# GMSL_DESERIALIZER.net
KiCad netlist of a schematic drawn in Altium Designer
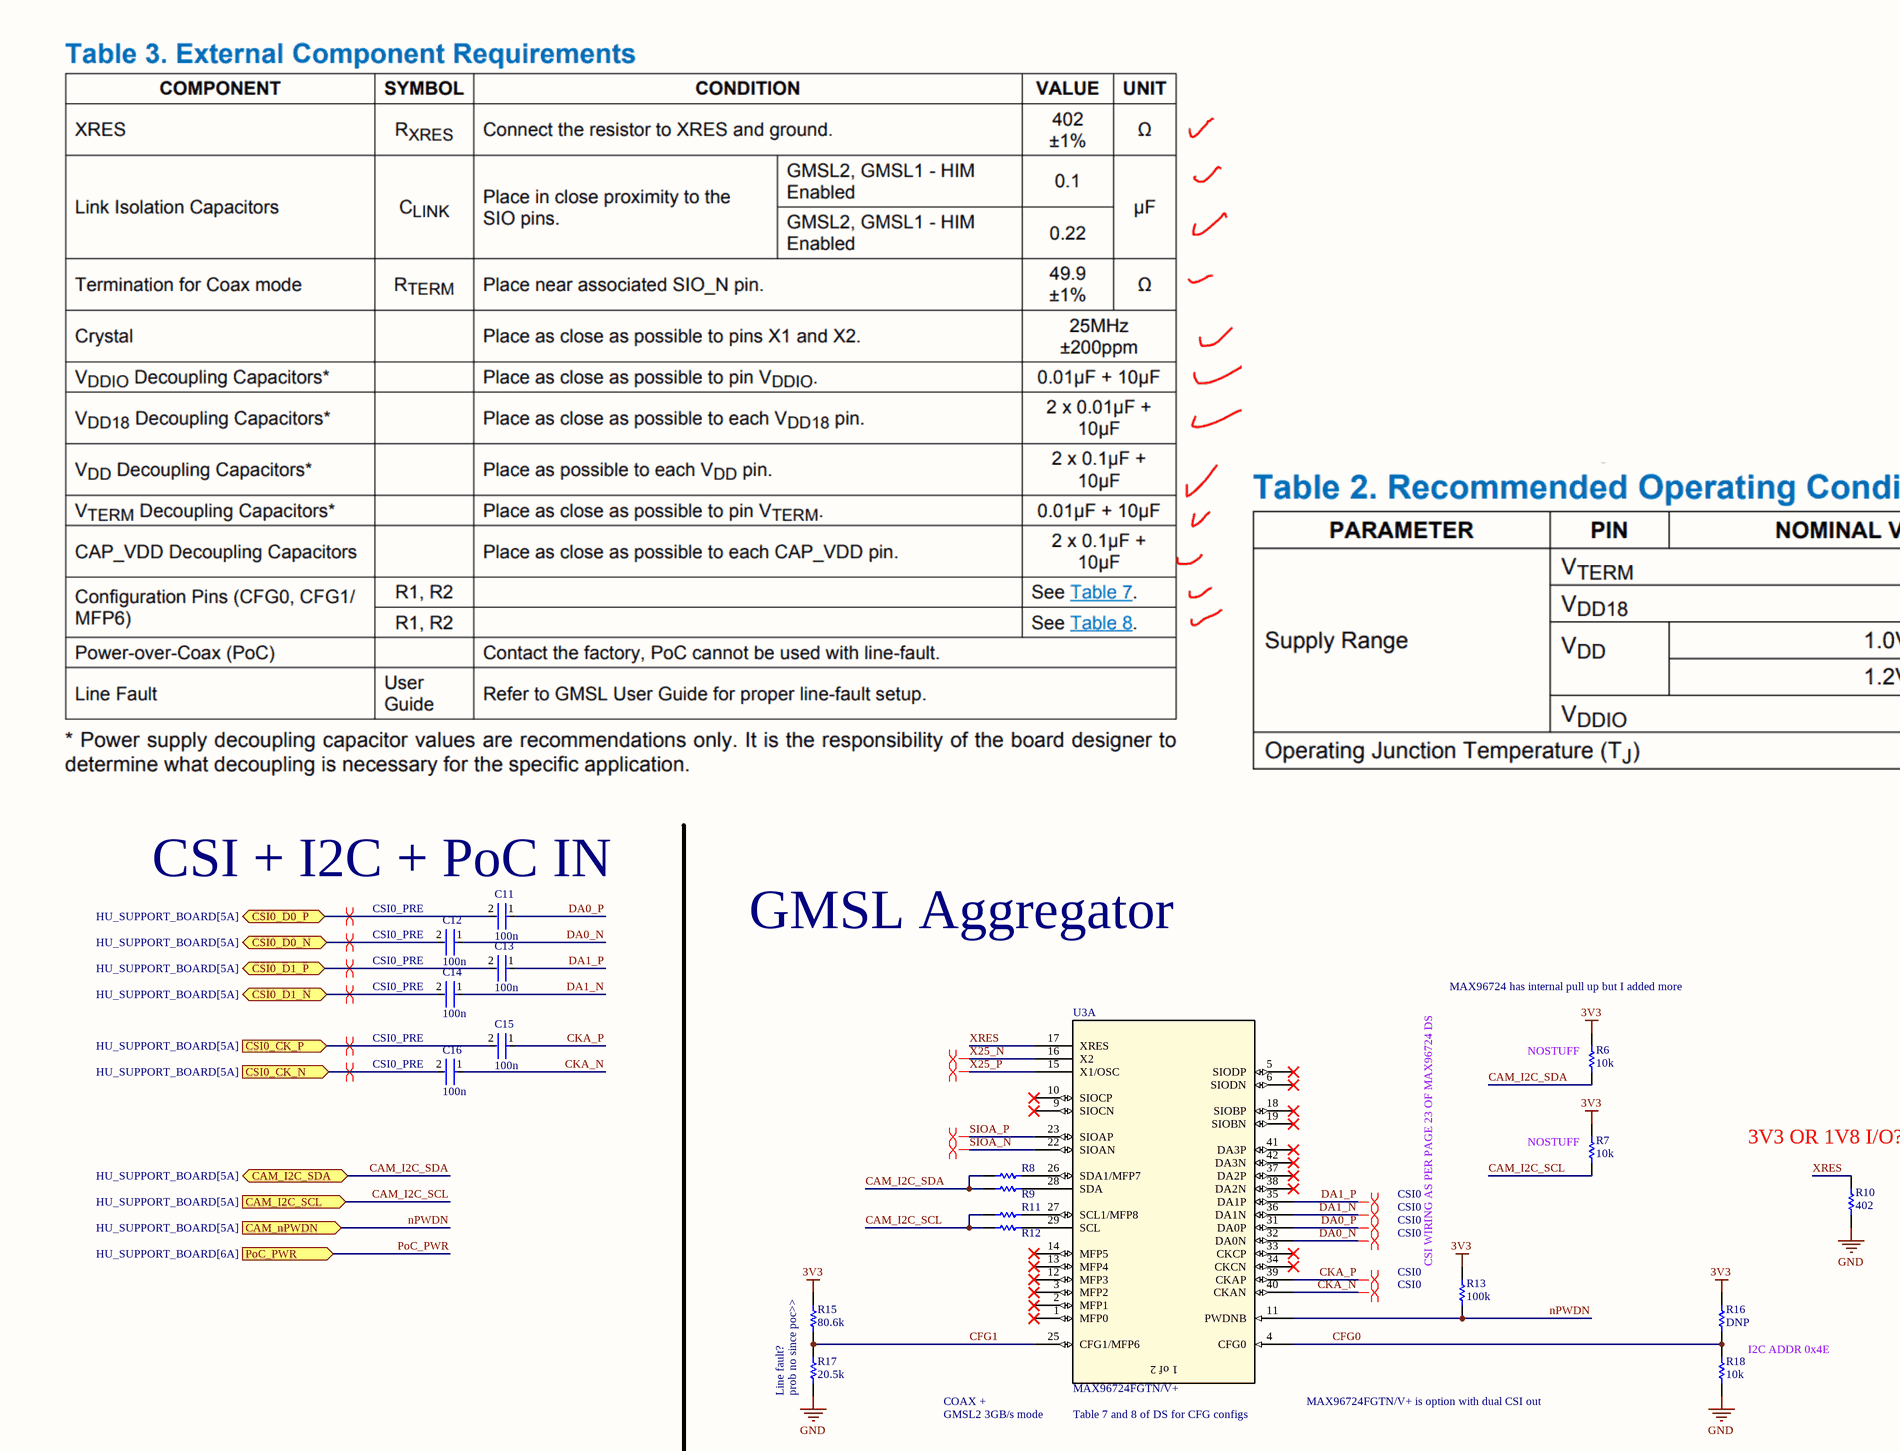
[diagram p0: GMSL_DESERIALIZER.SchDoc, top left]
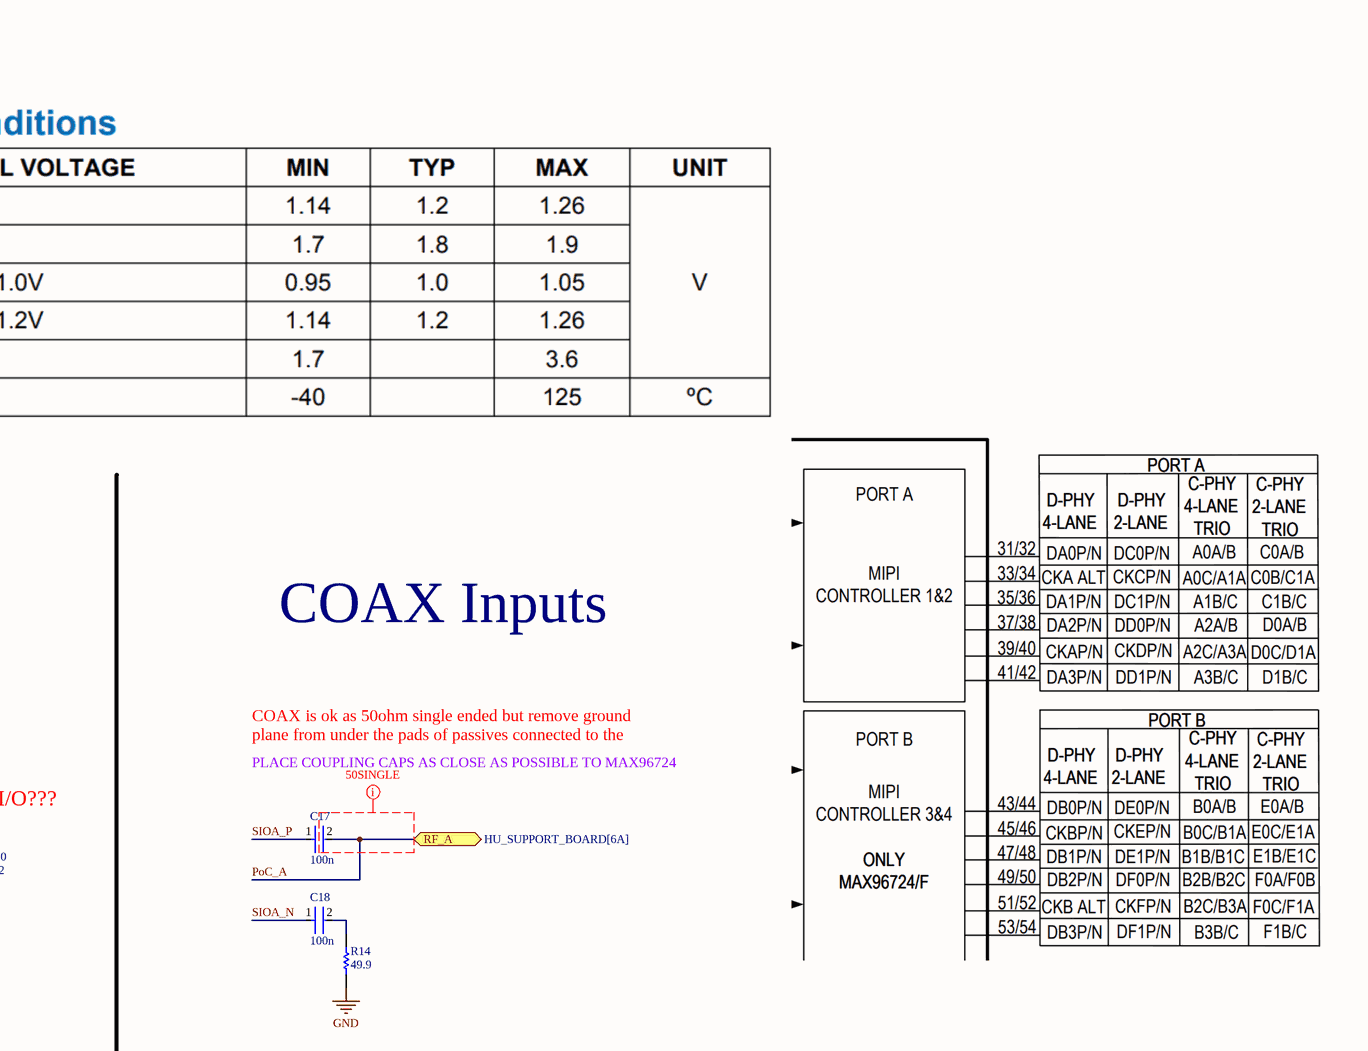
[diagram p1: GMSL_DESERIALIZER.SchDoc, top right]
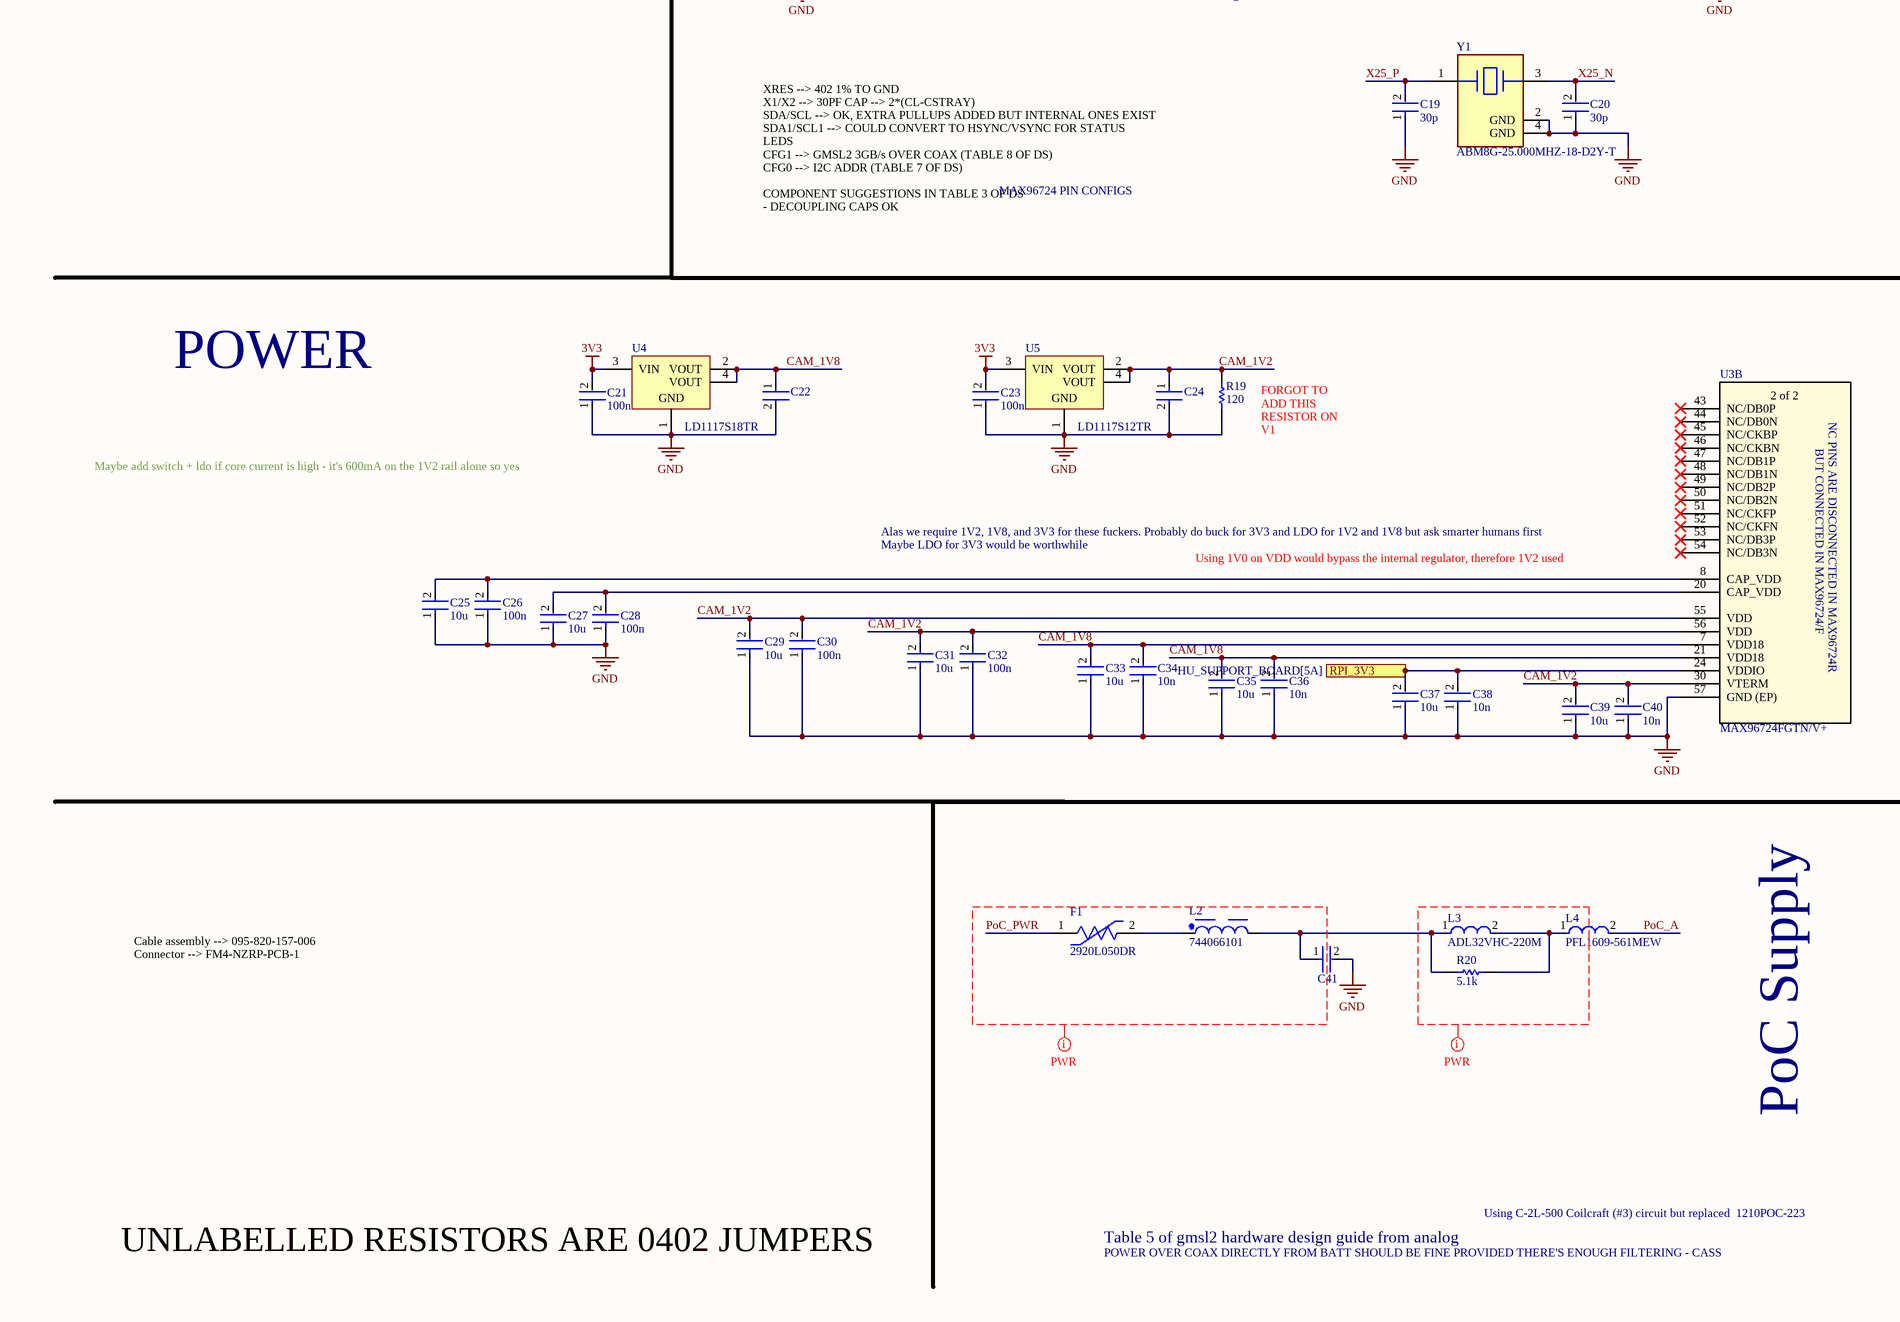
[diagram p2: GMSL_DESERIALIZER.SchDoc, bottom left]
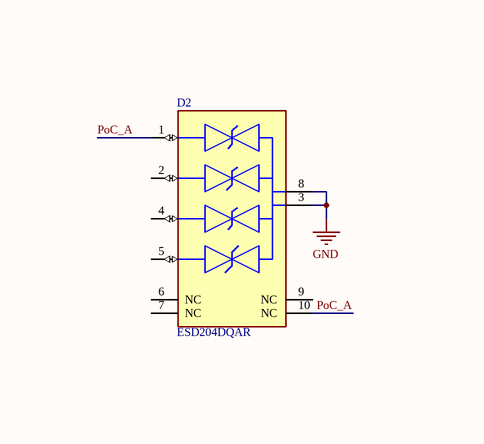
[diagram p3: GMSL_DESERIALIZER.SchDoc, bottom right]

(export (version "E")
  (design (tool "Eeschema 10.0.6"))
  (components
    (comp (ref "C11")
      (value "100n")
      (footprint "FP-0402-L_1_0_0_05-W_0_5-IPC_A")
      (description "LARGE PADS, 0402 CAP, CHANGE COMMENT TO MATCH REAL P/N")
      (libsource (lib "Space Concordia") (part "b4654b650e69147ec39a6b967a45e02"))
    )
    (comp (ref "C12")
      (value "100n")
      (footprint "FP-0402-L_1_0_0_05-W_0_5-IPC_A")
      (description "LARGE PADS, 0402 CAP, CHANGE COMMENT TO MATCH REAL P/N")
      (libsource (lib "Space Concordia") (part "b4654b650e69147ec39a6b967a45e02"))
    )
    (comp (ref "C13")
      (value "100n")
      (footprint "FP-0402-L_1_0_0_05-W_0_5-IPC_A")
      (description "LARGE PADS, 0402 CAP, CHANGE COMMENT TO MATCH REAL P/N")
      (libsource (lib "Space Concordia") (part "b4654b650e69147ec39a6b967a45e02"))
    )
    (comp (ref "C14")
      (value "100n")
      (footprint "FP-0402-L_1_0_0_05-W_0_5-IPC_A")
      (description "LARGE PADS, 0402 CAP, CHANGE COMMENT TO MATCH REAL P/N")
      (libsource (lib "Space Concordia") (part "b4654b650e69147ec39a6b967a45e02"))
    )
    (comp (ref "C15")
      (value "100n")
      (footprint "FP-0402-L_1_0_0_05-W_0_5-IPC_A")
      (description "LARGE PADS, 0402 CAP, CHANGE COMMENT TO MATCH REAL P/N")
      (libsource (lib "Space Concordia") (part "b4654b650e69147ec39a6b967a45e02"))
    )
    (comp (ref "C16")
      (value "100n")
      (footprint "FP-0402-L_1_0_0_05-W_0_5-IPC_A")
      (description "LARGE PADS, 0402 CAP, CHANGE COMMENT TO MATCH REAL P/N")
      (libsource (lib "Space Concordia") (part "b4654b650e69147ec39a6b967a45e02"))
    )
    (comp (ref "C17")
      (value "100n")
      (footprint "FP-0402-L_1_0_0_05-W_0_5-IPC_A")
      (description "LARGE PADS, 0402 CAP, CHANGE COMMENT TO MATCH REAL P/N")
      (libsource (lib "Space Concordia") (part "b4654b650e69147ec39a6b967a45e02"))
    )
    (comp (ref "C18")
      (value "100n")
      (footprint "FP-0402-L_1_0_0_05-W_0_5-IPC_A")
      (description "LARGE PADS, 0402 CAP, CHANGE COMMENT TO MATCH REAL P/N")
      (libsource (lib "Space Concordia") (part "b4654b650e69147ec39a6b967a45e02"))
    )
    (comp (ref "C19")
      (value "30p")
      (footprint "FP-0402-L_1_0_0_05-W_0_5-IPC_A")
      (description "LARGE PADS, 0402 CAP, CHANGE COMMENT TO MATCH REAL P/N")
      (libsource (lib "Space Concordia") (part "b4654b650e69147ec39a6b967a45e02"))
    )
    (comp (ref "C20")
      (value "30p")
      (footprint "FP-0402-L_1_0_0_05-W_0_5-IPC_A")
      (description "LARGE PADS, 0402 CAP, CHANGE COMMENT TO MATCH REAL P/N")
      (libsource (lib "Space Concordia") (part "b4654b650e69147ec39a6b967a45e02"))
    )
    (comp (ref "C21")
      (value "100n")
      (footprint "FP-0402-L_1_0_0_05-W_0_5-IPC_A")
      (description "LARGE PADS, 0402 CAP, CHANGE COMMENT TO MATCH REAL P/N")
      (libsource (lib "Space Concordia") (part "b4654b650e69147ec39a6b967a45e02"))
    )
    (comp (ref "C22")
      (value "GRM188R60J106ME47D")
      (footprint "FP-GRM188-0_1-e0_2_0_55-IPC_A")
      (description "Chip Multilayer Ceramic Capacitors for General Purpose, 0603, 10uF, X5R, 15%, 20%, 6.3V")
      (fields (field (name "VOLTAGE") "6.3V") (field (name "TOLERANCE") "20%"))
      (libsource (lib "Altium Content Vault") (part "02cd4be3c70576c341d710602a673aa"))
    )
    (comp (ref "C23")
      (value "100n")
      (footprint "FP-0402-L_1_0_0_05-W_0_5-IPC_A")
      (description "LARGE PADS, 0402 CAP, CHANGE COMMENT TO MATCH REAL P/N")
      (libsource (lib "Space Concordia") (part "b4654b650e69147ec39a6b967a45e02"))
    )
    (comp (ref "C24")
      (value "GRM188R60J106ME47D")
      (footprint "FP-GRM188-0_1-e0_2_0_55-IPC_A")
      (description "Chip Multilayer Ceramic Capacitors for General Purpose, 0603, 10uF, X5R, 15%, 20%, 6.3V")
      (fields (field (name "VOLTAGE") "6.3V") (field (name "TOLERANCE") "20%"))
      (libsource (lib "Altium Content Vault") (part "02cd4be3c70576c341d710602a673aa"))
    )
    (comp (ref "C25")
      (value "10u")
      (footprint "FP-0402-L_1_0_0_05-W_0_5-IPC_A")
      (description "LARGE PADS, 0402 CAP, CHANGE COMMENT TO MATCH REAL P/N")
      (libsource (lib "Space Concordia") (part "b4654b650e69147ec39a6b967a45e02"))
    )
    (comp (ref "C26")
      (value "100n")
      (footprint "FP-0402-L_1_0_0_05-W_0_5-IPC_A")
      (description "LARGE PADS, 0402 CAP, CHANGE COMMENT TO MATCH REAL P/N")
      (libsource (lib "Space Concordia") (part "b4654b650e69147ec39a6b967a45e02"))
    )
    (comp (ref "C27")
      (value "10u")
      (footprint "FP-0402-L_1_0_0_05-W_0_5-IPC_A")
      (description "LARGE PADS, 0402 CAP, CHANGE COMMENT TO MATCH REAL P/N")
      (libsource (lib "Space Concordia") (part "b4654b650e69147ec39a6b967a45e02"))
    )
    (comp (ref "C28")
      (value "100n")
      (footprint "FP-0402-L_1_0_0_05-W_0_5-IPC_A")
      (description "LARGE PADS, 0402 CAP, CHANGE COMMENT TO MATCH REAL P/N")
      (libsource (lib "Space Concordia") (part "b4654b650e69147ec39a6b967a45e02"))
    )
    (comp (ref "C29")
      (value "10u")
      (footprint "FP-0402-L_1_0_0_05-W_0_5-IPC_A")
      (description "LARGE PADS, 0402 CAP, CHANGE COMMENT TO MATCH REAL P/N")
      (libsource (lib "Space Concordia") (part "b4654b650e69147ec39a6b967a45e02"))
    )
    (comp (ref "C30")
      (value "100n")
      (footprint "FP-0402-L_1_0_0_05-W_0_5-IPC_A")
      (description "LARGE PADS, 0402 CAP, CHANGE COMMENT TO MATCH REAL P/N")
      (libsource (lib "Space Concordia") (part "b4654b650e69147ec39a6b967a45e02"))
    )
    (comp (ref "C31")
      (value "10u")
      (footprint "FP-0402-L_1_0_0_05-W_0_5-IPC_A")
      (description "LARGE PADS, 0402 CAP, CHANGE COMMENT TO MATCH REAL P/N")
      (libsource (lib "Space Concordia") (part "b4654b650e69147ec39a6b967a45e02"))
    )
    (comp (ref "C32")
      (value "100n")
      (footprint "FP-0402-L_1_0_0_05-W_0_5-IPC_A")
      (description "LARGE PADS, 0402 CAP, CHANGE COMMENT TO MATCH REAL P/N")
      (libsource (lib "Space Concordia") (part "b4654b650e69147ec39a6b967a45e02"))
    )
    (comp (ref "C33")
      (value "10u")
      (footprint "FP-0402-L_1_0_0_05-W_0_5-IPC_A")
      (description "LARGE PADS, 0402 CAP, CHANGE COMMENT TO MATCH REAL P/N")
      (libsource (lib "Space Concordia") (part "b4654b650e69147ec39a6b967a45e02"))
    )
    (comp (ref "C34")
      (value "10n")
      (footprint "FP-0402-L_1_0_0_05-W_0_5-IPC_A")
      (description "LARGE PADS, 0402 CAP, CHANGE COMMENT TO MATCH REAL P/N")
      (libsource (lib "Space Concordia") (part "b4654b650e69147ec39a6b967a45e02"))
    )
    (comp (ref "C35")
      (value "10u")
      (footprint "FP-0402-L_1_0_0_05-W_0_5-IPC_A")
      (description "LARGE PADS, 0402 CAP, CHANGE COMMENT TO MATCH REAL P/N")
      (libsource (lib "Space Concordia") (part "b4654b650e69147ec39a6b967a45e02"))
    )
    (comp (ref "C36")
      (value "10n")
      (footprint "FP-0402-L_1_0_0_05-W_0_5-IPC_A")
      (description "LARGE PADS, 0402 CAP, CHANGE COMMENT TO MATCH REAL P/N")
      (libsource (lib "Space Concordia") (part "b4654b650e69147ec39a6b967a45e02"))
    )
    (comp (ref "C37")
      (value "10u")
      (footprint "FP-0402-L_1_0_0_05-W_0_5-IPC_A")
      (description "LARGE PADS, 0402 CAP, CHANGE COMMENT TO MATCH REAL P/N")
      (libsource (lib "Space Concordia") (part "b4654b650e69147ec39a6b967a45e02"))
    )
    (comp (ref "C38")
      (value "10n")
      (footprint "FP-0402-L_1_0_0_05-W_0_5-IPC_A")
      (description "LARGE PADS, 0402 CAP, CHANGE COMMENT TO MATCH REAL P/N")
      (libsource (lib "Space Concordia") (part "b4654b650e69147ec39a6b967a45e02"))
    )
    (comp (ref "C39")
      (value "10u")
      (footprint "FP-0402-L_1_0_0_05-W_0_5-IPC_A")
      (description "LARGE PADS, 0402 CAP, CHANGE COMMENT TO MATCH REAL P/N")
      (libsource (lib "Space Concordia") (part "b4654b650e69147ec39a6b967a45e02"))
    )
    (comp (ref "C40")
      (value "10n")
      (footprint "FP-0402-L_1_0_0_05-W_0_5-IPC_A")
      (description "LARGE PADS, 0402 CAP, CHANGE COMMENT TO MATCH REAL P/N")
      (libsource (lib "Space Concordia") (part "b4654b650e69147ec39a6b967a45e02"))
    )
    (comp (ref "C41")
      (value "GRM21BR61E226ME44L")
      (footprint "FP-GRM21B-0_2-e0_2_0_7-IPC_B")
      (description "Chip Multilayer Ceramic Capacitors for General Purpose, 0805, 22uF, X5R, 15%, 20%, 25V")
      (fields (field (name "TOLERANCE") "20%") (field (name "VOLTAGE") "25V"))
      (libsource (lib "Altium Content Vault") (part "b4654b650e69147ec39a6b967a45e02"))
    )
    (comp (ref "D2")
      (value "ESD204DQAR")
      (footprint "FP-DQA0010A-MFG")
      (description "4-CHANNEL LOW-CAPACITANCE SURGE")
      (fields
        (field (name "MANUFACTURER") "Texas Instruments")
        (field (name "OCTOPART") "https://octopart.com/esd204dqar-texas+instruments-89917476")
      )
      (libsource (lib "Altium Content Vault") (part "1465e58c1818c7767b55926832f0bf5"))
    )
    (comp (ref "F1")
      (value "2920L050DR")
      (footprint "FP-2920L050DR-MFG")
      (description "PTC RESET FUSE 60V 500MA 2920")
      (libsource (lib "Altium Content Vault") (part "1c6d77a0208143737455a0c7eb396be"))
    )
    (comp (ref "L2")
      (value "744066101")
      (footprint "WE-TPC_1038")
      (fields (field (name "TOLERANCE") "30%"))
      (libsource (lib "Altium Content Vault") (part "Inductor - 2"))
    )
    (comp (ref "L3")
      (value "ADL32VHC-220M")
      (footprint "FP-1210POC-MFG")
      (description "NOT COILCRAFT - ACTUAL P# --> ADL32VHC-220M\r\n - Power Injection Chokes for PoC")
      (fields
        (field (name "MANUFACTURER") "coilcraft")
        (field (name "OCTOPART") "https://octopart.com/1210poc-223mrc-coilcraft-103207315")
      )
      (libsource (lib "Altium Content Vault") (part "725321dda6339637d4d059423bc1c3c"))
    )
    (comp (ref "L4")
      (value "PFL1609-561MEW")
      (footprint "FP-PFL1609-MFG")
      (description "Fixed Inductors PFL1609 Low Profile 0.56 uH 20 % 1.4 A")
      (fields (field (name "MANUFACTURER") "coilcraft") (field (name "TOLERANCE") "20%"))
      (libsource (lib "Altium Content Vault") (part "725321dda6339637d4d059423bc1c3c"))
    )
    (comp (ref "R6")
      (value "10k")
      (footprint "R0603B")
      (description "Resistor")
      (libsource (lib "Space Concordia") (part "Resistor"))
    )
    (comp (ref "R7")
      (value "10k")
      (footprint "R0603B")
      (description "Resistor")
      (libsource (lib "Space Concordia") (part "Resistor"))
    )
    (comp (ref "R8")
      (value "0402 JUMPER")
      (footprint "RESC1005X40X25ML05T05")
      (description "READ THE NAME")
      (libsource (lib "Space Concordia") (part "CMP-009-00206-2"))
    )
    (comp (ref "R9")
      (value "0402 JUMPER")
      (footprint "RESC1005X40X25ML05T05")
      (description "READ THE NAME")
      (libsource (lib "Space Concordia") (part "CMP-009-00206-2"))
    )
    (comp (ref "R10")
      (value "402")
      (footprint "R0603B")
      (description "Resistor")
      (libsource (lib "Space Concordia") (part "Resistor"))
    )
    (comp (ref "R11")
      (value "0402 JUMPER")
      (footprint "RESC1005X40X25ML05T05")
      (description "READ THE NAME")
      (libsource (lib "Space Concordia") (part "CMP-009-00206-2"))
    )
    (comp (ref "R12")
      (value "0402 JUMPER")
      (footprint "RESC1005X40X25ML05T05")
      (description "READ THE NAME")
      (libsource (lib "Space Concordia") (part "CMP-009-00206-2"))
    )
    (comp (ref "R13")
      (value "100k")
      (footprint "R0603B")
      (description "Resistor")
      (libsource (lib "Space Concordia") (part "Resistor"))
    )
    (comp (ref "R14")
      (value "49.9")
      (footprint "R0603B")
      (description "Resistor")
      (libsource (lib "Space Concordia") (part "Resistor"))
    )
    (comp (ref "R15")
      (value "80.6k")
      (footprint "R0603B")
      (description "Resistor")
      (libsource (lib "Space Concordia") (part "Resistor"))
    )
    (comp (ref "R16")
      (value "DNP")
      (footprint "R0603B")
      (description "Resistor")
      (libsource (lib "Space Concordia") (part "Resistor"))
    )
    (comp (ref "R17")
      (value "20.5k")
      (footprint "R0603B")
      (description "Resistor")
      (libsource (lib "Space Concordia") (part "Resistor"))
    )
    (comp (ref "R18")
      (value "10k")
      (footprint "R0603B")
      (description "Resistor")
      (libsource (lib "Space Concordia") (part "Resistor"))
    )
    (comp (ref "R19")
      (value "120")
      (footprint "R0603B")
      (description "Resistor")
      (libsource (lib "Space Concordia") (part "Resistor"))
    )
    (comp (ref "R20")
      (value "5.1k")
      (footprint "R0603B")
      (description "Resistor")
      (libsource (lib "Space Concordia") (part "Resistor"))
    )
    (comp (ref "U3")
      (value "MAX96724FGTN/V+")
      (footprint "MAX96724FGTN_V+-Footprint-1")
      (description "Quad Tunneling GMSL2/1 to CSI-2 Deserializer")
      (libsource (lib "") (part "MAX96724FGTN_V+-Symbol-1_1"))
    )
    (comp (ref "U4")
      (value "LD1117S18TR")
      (footprint "SOT-223_M")
      (description "Fixed Low Drop Positive Voltage Regulator, 1.8V, 4-Pin SOT-223, Tape and Reel")
      (libsource (lib "Altium Content Vault") (part "PM-REG-LD1117-SOT4"))
    )
    (comp (ref "U5")
      (value "LD1117S12TR")
      (footprint "SOT-223_M")
      (description "Fixed Low Drop Positive Voltage Regulator, 1.2V, 4-Pin SOT-223, Tape and Reel")
      (libsource (lib "Altium Content Vault") (part "PM-REG-LD1117-SOT4"))
    )
    (comp (ref "Y1")
      (value "ABM8G-25.000MHZ-18-D2Y-T")
      (footprint "FP-ABM8G-MFG")
      (description "Crystal 25MHz ±20ppm (Tol) ±30ppm (Stability) 18pF FUND 60Ω 4-Pin SMD T/R")
      (fields (field (name "TOLERANCE") "20ppm"))
      (libsource (lib "Altium Content Vault") (part "48e526d86b7f2615d98721063c72f49"))
    )
  )
  (nets
    (net (code "1") (name "/CAM_1V2") (class "Default")
      (node (ref "C24") (pin "1") (pinfunction "1_1") (pintype "passive"))
      (node (ref "C29") (pin "2") (pinfunction "2_2") (pintype "passive"))
      (node (ref "C30") (pin "2") (pinfunction "2_2") (pintype "passive"))
      (node (ref "C31") (pin "2") (pinfunction "2_2") (pintype "passive"))
      (node (ref "C32") (pin "2") (pinfunction "2_2") (pintype "passive"))
      (node (ref "C39") (pin "2") (pinfunction "2_2") (pintype "passive"))
      (node (ref "C40") (pin "2") (pinfunction "2_2") (pintype "passive"))
      (node (ref "R19") (pin "1") (pinfunction "1_1") (pintype "passive"))
      (node (ref "U3") (pin "30") (pinfunction "VTERM_30") (pintype "power_in"))
      (node (ref "U3") (pin "55") (pinfunction "VDD_55") (pintype "power_in"))
      (node (ref "U3") (pin "56") (pinfunction "VDD_56") (pintype "power_in"))
      (node (ref "U5") (pin "2") (pinfunction "VOUT_2") (pintype "power_in"))
      (node (ref "U5") (pin "4") (pinfunction "VOUT_4") (pintype "power_in"))
    )
    (net (code "2") (name "/CAM_1V8") (class "Default")
      (node (ref "C22") (pin "1") (pinfunction "1_1") (pintype "passive"))
      (node (ref "C33") (pin "2") (pinfunction "2_2") (pintype "passive"))
      (node (ref "C34") (pin "2") (pinfunction "2_2") (pintype "passive"))
      (node (ref "C35") (pin "2") (pinfunction "2_2") (pintype "passive"))
      (node (ref "C36") (pin "2") (pinfunction "2_2") (pintype "passive"))
      (node (ref "U3") (pin "21") (pinfunction "VDD18_21") (pintype "power_in"))
      (node (ref "U3") (pin "7") (pinfunction "VDD18_7") (pintype "power_in"))
      (node (ref "U4") (pin "2") (pinfunction "VOUT_2") (pintype "power_in"))
      (node (ref "U4") (pin "4") (pinfunction "VOUT_4") (pintype "power_in"))
    )
    (net (code "3") (name "/CAM_I2C_SCL") (class "Default")
      (node (ref "R11") (pin "1") (pinfunction "1_1") (pintype "passive"))
      (node (ref "R12") (pin "1") (pinfunction "1_1") (pintype "passive"))
      (node (ref "R7") (pin "1") (pinfunction "1_1") (pintype "passive"))
    )
    (net (code "4") (name "/CAM_I2C_SDA") (class "Default")
      (node (ref "R6") (pin "1") (pinfunction "1_1") (pintype "passive"))
      (node (ref "R8") (pin "1") (pinfunction "1_1") (pintype "passive"))
      (node (ref "R9") (pin "1") (pinfunction "1_1") (pintype "passive"))
    )
    (net (code "5") (name "/CFG0") (class "Default")
      (node (ref "R16") (pin "1") (pinfunction "1_1") (pintype "passive"))
      (node (ref "R18") (pin "2") (pinfunction "2_2") (pintype "passive"))
      (node (ref "U3") (pin "4") (pinfunction "CFG0_4") (pintype "input"))
    )
    (net (code "6") (name "/CFG1") (class "Default")
      (node (ref "R15") (pin "1") (pinfunction "1_1") (pintype "passive"))
      (node (ref "R17") (pin "2") (pinfunction "2_2") (pintype "passive"))
      (node (ref "U3") (pin "25") (pinfunction "CFG1/MFP6_25") (pintype "bidirectional"))
    )
    (net (code "7") (name "/CKA_N") (class "Default")
      (node (ref "C16") (pin "1") (pinfunction "1_1") (pintype "passive"))
      (node (ref "U3") (pin "40") (pinfunction "CKAN_40") (pintype "bidirectional"))
    )
    (net (code "8") (name "/CKA_P") (class "Default")
      (node (ref "C15") (pin "1") (pinfunction "1_1") (pintype "passive"))
      (node (ref "U3") (pin "39") (pinfunction "CKAP_39") (pintype "bidirectional"))
    )
    (net (code "9") (name "/CSI0_CK_N") (class "Default")
      (node (ref "C16") (pin "2") (pinfunction "2_2") (pintype "passive"))
    )
    (net (code "10") (name "/CSI0_CK_P") (class "Default")
      (node (ref "C15") (pin "2") (pinfunction "2_2") (pintype "passive"))
    )
    (net (code "11") (name "/CSI0_D0_N") (class "Default")
      (node (ref "C12") (pin "2") (pinfunction "2_2") (pintype "passive"))
    )
    (net (code "12") (name "/CSI0_D0_P") (class "Default")
      (node (ref "C11") (pin "2") (pinfunction "2_2") (pintype "passive"))
    )
    (net (code "13") (name "/CSI0_D1_N") (class "Default")
      (node (ref "C14") (pin "2") (pinfunction "2_2") (pintype "passive"))
    )
    (net (code "14") (name "/CSI0_D1_P") (class "Default")
      (node (ref "C13") (pin "2") (pinfunction "2_2") (pintype "passive"))
    )
    (net (code "15") (name "/DA0_N") (class "Default")
      (node (ref "C12") (pin "1") (pinfunction "1_1") (pintype "passive"))
      (node (ref "U3") (pin "32") (pinfunction "DA0N_32") (pintype "bidirectional"))
    )
    (net (code "16") (name "/DA0_P") (class "Default")
      (node (ref "C11") (pin "1") (pinfunction "1_1") (pintype "passive"))
      (node (ref "U3") (pin "31") (pinfunction "DA0P_31") (pintype "bidirectional"))
    )
    (net (code "17") (name "/DA1_N") (class "Default")
      (node (ref "C14") (pin "1") (pinfunction "1_1") (pintype "passive"))
      (node (ref "U3") (pin "36") (pinfunction "DA1N_36") (pintype "bidirectional"))
    )
    (net (code "18") (name "/DA1_P") (class "Default")
      (node (ref "C13") (pin "1") (pinfunction "1_1") (pintype "passive"))
      (node (ref "U3") (pin "35") (pinfunction "DA1P_35") (pintype "bidirectional"))
    )
    (net (code "19") (name "/PoC_A") (class "Default")
      (node (ref "C17") (pin "2") (pinfunction "2_2") (pintype "passive"))
      (node (ref "D2") (pin "1") (pinfunction "IO1_1") (pintype "bidirectional"))
      (node (ref "D2") (pin "10") (pinfunction "NC_10") (pintype "passive"))
      (node (ref "L4") (pin "2") (pinfunction "2_2") (pintype "passive"))
    )
    (net (code "20") (name "/PoC_PWR") (class "Default")
      (node (ref "F1") (pin "1") (pinfunction "1_1") (pintype "passive"))
    )
    (net (code "21") (name "/RPI_3V3") (class "Default")
      (node (ref "C37") (pin "2") (pinfunction "2_2") (pintype "passive"))
      (node (ref "C38") (pin "2") (pinfunction "2_2") (pintype "passive"))
      (node (ref "U3") (pin "24") (pinfunction "VDDIO_24") (pintype "power_in"))
    )
    (net (code "22") (name "/SIOA_N") (class "Default")
      (node (ref "C18") (pin "1") (pinfunction "1_1") (pintype "passive"))
      (node (ref "U3") (pin "22") (pinfunction "SIOAN_22") (pintype "bidirectional"))
    )
    (net (code "23") (name "/SIOA_P") (class "Default")
      (node (ref "C17") (pin "1") (pinfunction "1_1") (pintype "passive"))
      (node (ref "U3") (pin "23") (pinfunction "SIOAP_23") (pintype "bidirectional"))
    )
    (net (code "24") (name "/X25_N") (class "Default")
      (node (ref "C20") (pin "2") (pinfunction "2_2") (pintype "passive"))
      (node (ref "U3") (pin "16") (pinfunction "X2_16") (pintype "passive"))
      (node (ref "Y1") (pin "3") (pinfunction "3_3") (pintype "passive"))
    )
    (net (code "25") (name "/X25_P") (class "Default")
      (node (ref "C19") (pin "2") (pinfunction "2_2") (pintype "passive"))
      (node (ref "U3") (pin "15") (pinfunction "X1/OSC_15") (pintype "passive"))
      (node (ref "Y1") (pin "1") (pinfunction "1_1") (pintype "passive"))
    )
    (net (code "26") (name "/XRES") (class "Default")
      (node (ref "R10") (pin "2") (pinfunction "2_2") (pintype "passive"))
      (node (ref "U3") (pin "17") (pinfunction "XRES_17") (pintype "passive"))
    )
    (net (code "27") (name "/nPWDN") (class "Default")
      (node (ref "R13") (pin "1") (pinfunction "1_1") (pintype "passive"))
      (node (ref "U3") (pin "11") (pinfunction "PWDNB_11") (pintype "input"))
    )
    (net (code "28") (name "3V3") (class "Default")
      (node (ref "C21") (pin "2") (pinfunction "2_2") (pintype "passive"))
      (node (ref "C23") (pin "2") (pinfunction "2_2") (pintype "passive"))
      (node (ref "R13") (pin "2") (pinfunction "2_2") (pintype "passive"))
      (node (ref "R15") (pin "2") (pinfunction "2_2") (pintype "passive"))
      (node (ref "R16") (pin "2") (pinfunction "2_2") (pintype "passive"))
      (node (ref "R6") (pin "2") (pinfunction "2_2") (pintype "passive"))
      (node (ref "R7") (pin "2") (pinfunction "2_2") (pintype "passive"))
      (node (ref "U4") (pin "3") (pinfunction "VIN_3") (pintype "power_in"))
      (node (ref "U5") (pin "3") (pinfunction "VIN_3") (pintype "power_in"))
    )
    (net (code "29") (name "GND") (class "Default")
      (node (ref "C19") (pin "1") (pinfunction "1_1") (pintype "passive"))
      (node (ref "C20") (pin "1") (pinfunction "1_1") (pintype "passive"))
      (node (ref "C21") (pin "1") (pinfunction "1_1") (pintype "passive"))
      (node (ref "C22") (pin "2") (pinfunction "2_2") (pintype "passive"))
      (node (ref "C23") (pin "1") (pinfunction "1_1") (pintype "passive"))
      (node (ref "C24") (pin "2") (pinfunction "2_2") (pintype "passive"))
      (node (ref "C25") (pin "1") (pinfunction "1_1") (pintype "passive"))
      (node (ref "C26") (pin "1") (pinfunction "1_1") (pintype "passive"))
      (node (ref "C27") (pin "1") (pinfunction "1_1") (pintype "passive"))
      (node (ref "C28") (pin "1") (pinfunction "1_1") (pintype "passive"))
      (node (ref "C29") (pin "1") (pinfunction "1_1") (pintype "passive"))
      (node (ref "C30") (pin "1") (pinfunction "1_1") (pintype "passive"))
      (node (ref "C31") (pin "1") (pinfunction "1_1") (pintype "passive"))
      (node (ref "C32") (pin "1") (pinfunction "1_1") (pintype "passive"))
      (node (ref "C33") (pin "1") (pinfunction "1_1") (pintype "passive"))
      (node (ref "C34") (pin "1") (pinfunction "1_1") (pintype "passive"))
      (node (ref "C35") (pin "1") (pinfunction "1_1") (pintype "passive"))
      (node (ref "C36") (pin "1") (pinfunction "1_1") (pintype "passive"))
      (node (ref "C37") (pin "1") (pinfunction "1_1") (pintype "passive"))
      (node (ref "C38") (pin "1") (pinfunction "1_1") (pintype "passive"))
      (node (ref "C39") (pin "1") (pinfunction "1_1") (pintype "passive"))
      (node (ref "C40") (pin "1") (pinfunction "1_1") (pintype "passive"))
      (node (ref "C41") (pin "2") (pinfunction "2_2") (pintype "passive"))
      (node (ref "D2") (pin "3") (pinfunction "GND_3") (pintype "power_in"))
      (node (ref "D2") (pin "8") (pinfunction "GND_8") (pintype "power_in"))
      (node (ref "R10") (pin "1") (pinfunction "1_1") (pintype "passive"))
      (node (ref "R14") (pin "1") (pinfunction "1_1") (pintype "passive"))
      (node (ref "R17") (pin "1") (pinfunction "1_1") (pintype "passive"))
      (node (ref "R18") (pin "1") (pinfunction "1_1") (pintype "passive"))
      (node (ref "R19") (pin "2") (pinfunction "2_2") (pintype "passive"))
      (node (ref "U3") (pin "57") (pinfunction "GND_(EP)_57") (pintype "power_in"))
      (node (ref "U4") (pin "1") (pinfunction "GND_1") (pintype "power_in"))
      (node (ref "U5") (pin "1") (pinfunction "GND_1") (pintype "power_in"))
      (node (ref "Y1") (pin "2") (pinfunction "GND_2") (pintype "power_in"))
      (node (ref "Y1") (pin "4") (pinfunction "GND_4") (pintype "power_in"))
    )
    (net (code "30") (name "Net-(C18-Pad2)") (class "Default")
      (node (ref "C18") (pin "2") (pinfunction "2_2") (pintype "passive"))
      (node (ref "R14") (pin "2") (pinfunction "2_2") (pintype "passive"))
    )
    (net (code "31") (name "Net-(C25-Pad2)") (class "Default")
      (node (ref "C25") (pin "2") (pinfunction "2_2") (pintype "passive"))
      (node (ref "C26") (pin "2") (pinfunction "2_2") (pintype "passive"))
      (node (ref "U3") (pin "8") (pinfunction "CAP_VDD_8") (pintype "power_in"))
    )
    (net (code "32") (name "Net-(C27-Pad2)") (class "Default")
      (node (ref "C27") (pin "2") (pinfunction "2_2") (pintype "passive"))
      (node (ref "C28") (pin "2") (pinfunction "2_2") (pintype "passive"))
      (node (ref "U3") (pin "20") (pinfunction "CAP_VDD_20") (pintype "power_in"))
    )
    (net (code "33") (name "Net-(C41-Pad1)") (class "Default")
      (node (ref "C41") (pin "1") (pinfunction "1_1") (pintype "passive"))
      (node (ref "L2") (pin "2") (pinfunction "2_2") (pintype "passive"))
      (node (ref "L3") (pin "1") (pinfunction "1_1") (pintype "passive"))
      (node (ref "R20") (pin "2") (pinfunction "2_2") (pintype "passive"))
    )
    (net (code "34") (name "Net-(F1-Pad2)") (class "Default")
      (node (ref "F1") (pin "2") (pinfunction "2_2") (pintype "passive"))
      (node (ref "L2") (pin "1") (pinfunction "1_1") (pintype "passive"))
    )
    (net (code "35") (name "Net-(L3-Pad2)") (class "Default")
      (node (ref "L3") (pin "2") (pinfunction "2_2") (pintype "passive"))
      (node (ref "L4") (pin "1") (pinfunction "1_1") (pintype "passive"))
      (node (ref "R20") (pin "1") (pinfunction "1_1") (pintype "passive"))
    )
    (net (code "36") (name "Net-(U3A-SCL)") (class "Default")
      (node (ref "R12") (pin "2") (pinfunction "2_2") (pintype "passive"))
      (node (ref "U3") (pin "29") (pinfunction "SCL_29") (pintype "passive"))
    )
    (net (code "37") (name "Net-(U3A-SCL1{slash}MFP8)") (class "Default")
      (node (ref "R11") (pin "2") (pinfunction "2_2") (pintype "passive"))
      (node (ref "U3") (pin "27") (pinfunction "SCL1/MFP8_27") (pintype "bidirectional"))
    )
    (net (code "38") (name "Net-(U3A-SDA)") (class "Default")
      (node (ref "R9") (pin "2") (pinfunction "2_2") (pintype "passive"))
      (node (ref "U3") (pin "28") (pinfunction "SDA_28") (pintype "passive"))
    )
    (net (code "39") (name "Net-(U3A-SDA1{slash}MFP7)") (class "Default")
      (node (ref "R8") (pin "2") (pinfunction "2_2") (pintype "passive"))
      (node (ref "U3") (pin "26") (pinfunction "SDA1/MFP7_26") (pintype "bidirectional"))
    )
    (net (code "40") (name "unconnected-(D2-IO2-Pad2)") (class "Default")
      (node (ref "D2") (pin "2") (pinfunction "IO2_2") (pintype "bidirectional"))
    )
    (net (code "41") (name "unconnected-(D2-IO3-Pad4)") (class "Default")
      (node (ref "D2") (pin "4") (pinfunction "IO3_4") (pintype "bidirectional"))
    )
    (net (code "42") (name "unconnected-(D2-IO4-Pad5)") (class "Default")
      (node (ref "D2") (pin "5") (pinfunction "IO4_5") (pintype "bidirectional"))
    )
    (net (code "43") (name "unconnected-(D2-NC-Pad6)") (class "Default")
      (node (ref "D2") (pin "6") (pinfunction "NC_6") (pintype "passive"))
    )
    (net (code "44") (name "unconnected-(D2-NC-Pad7)") (class "Default")
      (node (ref "D2") (pin "7") (pinfunction "NC_7") (pintype "passive"))
    )
    (net (code "45") (name "unconnected-(D2-NC-Pad9)") (class "Default")
      (node (ref "D2") (pin "9") (pinfunction "NC_9") (pintype "passive"))
    )
    (net (code "46") (name "unconnected-(U3A-CKCN-Pad34)") (class "Default")
      (node (ref "U3") (pin "34") (pinfunction "CKCN_34") (pintype "bidirectional+no_connect"))
    )
    (net (code "47") (name "unconnected-(U3A-CKCP-Pad33)") (class "Default")
      (node (ref "U3") (pin "33") (pinfunction "CKCP_33") (pintype "bidirectional+no_connect"))
    )
    (net (code "48") (name "unconnected-(U3A-DA2N-Pad38)") (class "Default")
      (node (ref "U3") (pin "38") (pinfunction "DA2N_38") (pintype "bidirectional+no_connect"))
    )
    (net (code "49") (name "unconnected-(U3A-DA2P-Pad37)") (class "Default")
      (node (ref "U3") (pin "37") (pinfunction "DA2P_37") (pintype "bidirectional+no_connect"))
    )
    (net (code "50") (name "unconnected-(U3A-DA3N-Pad42)") (class "Default")
      (node (ref "U3") (pin "42") (pinfunction "DA3N_42") (pintype "bidirectional+no_connect"))
    )
    (net (code "51") (name "unconnected-(U3A-DA3P-Pad41)") (class "Default")
      (node (ref "U3") (pin "41") (pinfunction "DA3P_41") (pintype "bidirectional+no_connect"))
    )
    (net (code "52") (name "unconnected-(U3A-MFP0-Pad1)") (class "Default")
      (node (ref "U3") (pin "1") (pinfunction "MFP0_1") (pintype "bidirectional+no_connect"))
    )
    (net (code "53") (name "unconnected-(U3A-MFP1-Pad2)") (class "Default")
      (node (ref "U3") (pin "2") (pinfunction "MFP1_2") (pintype "bidirectional+no_connect"))
    )
    (net (code "54") (name "unconnected-(U3A-MFP2-Pad3)") (class "Default")
      (node (ref "U3") (pin "3") (pinfunction "MFP2_3") (pintype "bidirectional+no_connect"))
    )
    (net (code "55") (name "unconnected-(U3A-MFP3-Pad12)") (class "Default")
      (node (ref "U3") (pin "12") (pinfunction "MFP3_12") (pintype "bidirectional+no_connect"))
    )
    (net (code "56") (name "unconnected-(U3A-MFP4-Pad13)") (class "Default")
      (node (ref "U3") (pin "13") (pinfunction "MFP4_13") (pintype "bidirectional+no_connect"))
    )
    (net (code "57") (name "unconnected-(U3A-MFP5-Pad14)") (class "Default")
      (node (ref "U3") (pin "14") (pinfunction "MFP5_14") (pintype "bidirectional+no_connect"))
    )
    (net (code "58") (name "unconnected-(U3A-SIOBN-Pad19)") (class "Default")
      (node (ref "U3") (pin "19") (pinfunction "SIOBN_19") (pintype "bidirectional+no_connect"))
    )
    (net (code "59") (name "unconnected-(U3A-SIOBP-Pad18)") (class "Default")
      (node (ref "U3") (pin "18") (pinfunction "SIOBP_18") (pintype "bidirectional+no_connect"))
    )
    (net (code "60") (name "unconnected-(U3A-SIOCN-Pad9)") (class "Default")
      (node (ref "U3") (pin "9") (pinfunction "SIOCN_9") (pintype "bidirectional+no_connect"))
    )
    (net (code "61") (name "unconnected-(U3A-SIOCP-Pad10)") (class "Default")
      (node (ref "U3") (pin "10") (pinfunction "SIOCP_10") (pintype "bidirectional+no_connect"))
    )
    (net (code "62") (name "unconnected-(U3A-SIODN-Pad6)") (class "Default")
      (node (ref "U3") (pin "6") (pinfunction "SIODN_6") (pintype "bidirectional+no_connect"))
    )
    (net (code "63") (name "unconnected-(U3A-SIODP-Pad5)") (class "Default")
      (node (ref "U3") (pin "5") (pinfunction "SIODP_5") (pintype "bidirectional+no_connect"))
    )
    (net (code "64") (name "unconnected-(U3B-NC{slash}CKBN-Pad46)") (class "Default")
      (node (ref "U3") (pin "46") (pinfunction "NC/CKBN_46") (pintype "passive+no_connect"))
    )
    (net (code "65") (name "unconnected-(U3B-NC{slash}CKBP-Pad45)") (class "Default")
      (node (ref "U3") (pin "45") (pinfunction "NC/CKBP_45") (pintype "passive+no_connect"))
    )
    (net (code "66") (name "unconnected-(U3B-NC{slash}CKFN-Pad52)") (class "Default")
      (node (ref "U3") (pin "52") (pinfunction "NC/CKFN_52") (pintype "passive+no_connect"))
    )
    (net (code "67") (name "unconnected-(U3B-NC{slash}CKFP-Pad51)") (class "Default")
      (node (ref "U3") (pin "51") (pinfunction "NC/CKFP_51") (pintype "passive+no_connect"))
    )
    (net (code "68") (name "unconnected-(U3B-NC{slash}DB0N-Pad44)") (class "Default")
      (node (ref "U3") (pin "44") (pinfunction "NC/DB0N_44") (pintype "passive+no_connect"))
    )
    (net (code "69") (name "unconnected-(U3B-NC{slash}DB0P-Pad43)") (class "Default")
      (node (ref "U3") (pin "43") (pinfunction "NC/DB0P_43") (pintype "passive+no_connect"))
    )
    (net (code "70") (name "unconnected-(U3B-NC{slash}DB1N-Pad48)") (class "Default")
      (node (ref "U3") (pin "48") (pinfunction "NC/DB1N_48") (pintype "passive+no_connect"))
    )
    (net (code "71") (name "unconnected-(U3B-NC{slash}DB1P-Pad47)") (class "Default")
      (node (ref "U3") (pin "47") (pinfunction "NC/DB1P_47") (pintype "passive+no_connect"))
    )
    (net (code "72") (name "unconnected-(U3B-NC{slash}DB2N-Pad50)") (class "Default")
      (node (ref "U3") (pin "50") (pinfunction "NC/DB2N_50") (pintype "passive+no_connect"))
    )
    (net (code "73") (name "unconnected-(U3B-NC{slash}DB2P-Pad49)") (class "Default")
      (node (ref "U3") (pin "49") (pinfunction "NC/DB2P_49") (pintype "passive+no_connect"))
    )
    (net (code "74") (name "unconnected-(U3B-NC{slash}DB3N-Pad54)") (class "Default")
      (node (ref "U3") (pin "54") (pinfunction "NC/DB3N_54") (pintype "passive+no_connect"))
    )
    (net (code "75") (name "unconnected-(U3B-NC{slash}DB3P-Pad53)") (class "Default")
      (node (ref "U3") (pin "53") (pinfunction "NC/DB3P_53") (pintype "passive+no_connect"))
    )
  )
)
